# chinmay.net
KiCad netlist of a schematic drawn in EAGLE
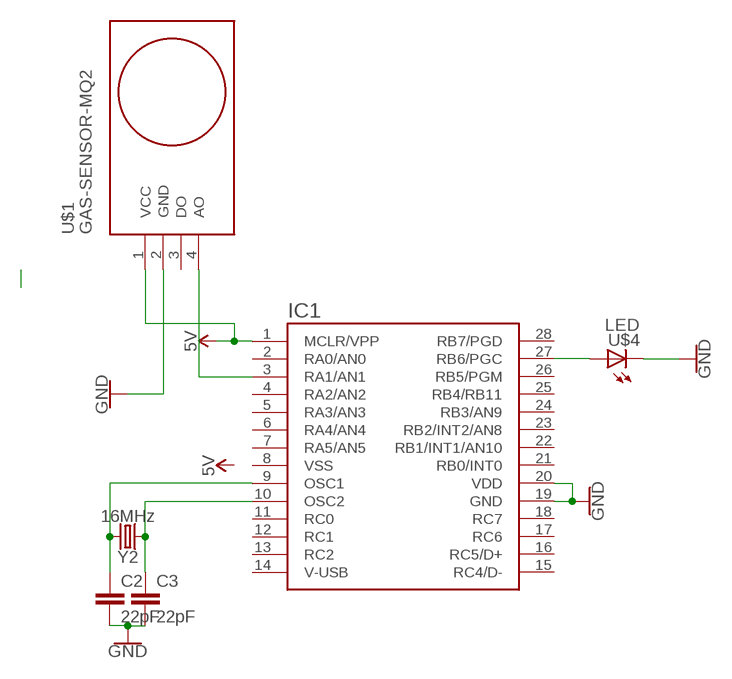
[diagram p0: schematic, sheet 1]

(export (version "E")
  (design (tool "Eeschema 10.0.6"))
  (components
    (comp (ref "C2")
      (value "22pF")
      (footprint "eagle-import:0603")
      (libsource (lib "eagle-import") (part "22PF-0603-50V-5%"))
    )
    (comp (ref "C3")
      (value "22pF")
      (footprint "eagle-import:0603")
      (libsource (lib "eagle-import") (part "22PF-0603-50V-5%"))
    )
    (comp (ref "IC1")
      (value "PIC18F2550SMD-28")
      (footprint "eagle-import:SO28")
      (libsource (lib "eagle-import") (part "PIC18F2550SMD-28"))
    )
    (comp (ref "U$1")
      (value "GAS-SENSOR-MQ2")
      (footprint "eagle-import:GAS-SENSOR-MQ2")
      (libsource (lib "eagle-import") (part "GAS-SENSOR-MQ2"))
    )
    (comp (ref "U$4")
      (value "LED")
      (footprint "eagle-import:HLMP-1790")
      (libsource (lib "eagle-import") (part "LED"))
    )
    (comp (ref "Y2")
      (value "16MHz")
      (footprint "eagle-import:HC49US")
      (libsource (lib "eagle-import") (part "CRYSTAL-16MHZPTH-HC49US"))
    )
  )
  (nets
    (net (code "1") (name "5V") (class "Default")
      (node (ref "IC1") (pin "1") (pinfunction "MCLR/VPP_1") (pintype "bidirectional"))
      (node (ref "U$1") (pin "1") (pinfunction "VCC_1") (pintype "power_in"))
    )
    (net (code "2") (name "GND") (class "Default")
      (node (ref "C2") (pin "2") (pinfunction "2_2") (pintype "passive"))
      (node (ref "C3") (pin "2") (pinfunction "2_2") (pintype "passive"))
      (node (ref "IC1") (pin "19") (pinfunction "GND_19") (pintype "bidirectional"))
      (node (ref "IC1") (pin "20") (pinfunction "VDD_20") (pintype "bidirectional"))
      (node (ref "U$1") (pin "2") (pinfunction "GND_2") (pintype "power_in"))
      (node (ref "U$4") (pin "C") (pinfunction "C_C") (pintype "passive"))
    )
    (net (code "3") (name "Net-(IC1-OSC1)") (class "Default")
      (node (ref "C2") (pin "1") (pinfunction "1_1") (pintype "passive"))
      (node (ref "IC1") (pin "9") (pinfunction "OSC1_9") (pintype "bidirectional"))
      (node (ref "Y2") (pin "2") (pinfunction "2_2") (pintype "passive"))
    )
    (net (code "4") (name "Net-(IC1-OSC2)") (class "Default")
      (node (ref "C3") (pin "1") (pinfunction "1_1") (pintype "passive"))
      (node (ref "IC1") (pin "10") (pinfunction "OSC2_10") (pintype "bidirectional"))
      (node (ref "Y2") (pin "1") (pinfunction "1_1") (pintype "passive"))
    )
    (net (code "5") (name "Net-(IC1-RA1{slash}AN1)") (class "Default")
      (node (ref "IC1") (pin "3") (pinfunction "RA1/AN1_3") (pintype "bidirectional"))
      (node (ref "U$1") (pin "4") (pinfunction "AO_4") (pintype "output"))
    )
    (net (code "6") (name "Net-(IC1-RB6{slash}PGC)") (class "Default")
      (node (ref "IC1") (pin "27") (pinfunction "RB6/PGC_27") (pintype "bidirectional"))
      (node (ref "U$4") (pin "A") (pinfunction "A_A") (pintype "passive"))
    )
    (net (code "7") (name "unconnected-(IC1-RA0{slash}AN0-Pad2)") (class "Default")
      (node (ref "IC1") (pin "2") (pinfunction "RA0/AN0_2") (pintype "bidirectional"))
    )
    (net (code "8") (name "unconnected-(IC1-RA2{slash}AN2-Pad4)") (class "Default")
      (node (ref "IC1") (pin "4") (pinfunction "RA2/AN2_4") (pintype "bidirectional"))
    )
    (net (code "9") (name "unconnected-(IC1-RA3{slash}AN3-Pad5)") (class "Default")
      (node (ref "IC1") (pin "5") (pinfunction "RA3/AN3_5") (pintype "bidirectional"))
    )
    (net (code "10") (name "unconnected-(IC1-RA4{slash}AN4-Pad6)") (class "Default")
      (node (ref "IC1") (pin "6") (pinfunction "RA4/AN4_6") (pintype "bidirectional"))
    )
    (net (code "11") (name "unconnected-(IC1-RA5{slash}AN5-Pad7)") (class "Default")
      (node (ref "IC1") (pin "7") (pinfunction "RA5/AN5_7") (pintype "bidirectional"))
    )
    (net (code "12") (name "unconnected-(IC1-RB0{slash}INT0-Pad21)") (class "Default")
      (node (ref "IC1") (pin "21") (pinfunction "RB0/INT0_21") (pintype "bidirectional"))
    )
    (net (code "13") (name "unconnected-(IC1-RB1{slash}INT1{slash}AN10-Pad22)") (class "Default")
      (node (ref "IC1") (pin "22") (pinfunction "RB1/INT1/AN10_22") (pintype "bidirectional"))
    )
    (net (code "14") (name "unconnected-(IC1-RB2{slash}INT2{slash}AN8-Pad23)") (class "Default")
      (node (ref "IC1") (pin "23") (pinfunction "RB2/INT2/AN8_23") (pintype "bidirectional"))
    )
    (net (code "15") (name "unconnected-(IC1-RB3{slash}AN9-Pad24)") (class "Default")
      (node (ref "IC1") (pin "24") (pinfunction "RB3/AN9_24") (pintype "bidirectional"))
    )
    (net (code "16") (name "unconnected-(IC1-RB4{slash}RB11-Pad25)") (class "Default")
      (node (ref "IC1") (pin "25") (pinfunction "RB4/RB11_25") (pintype "bidirectional"))
    )
    (net (code "17") (name "unconnected-(IC1-RB5{slash}PGM-Pad26)") (class "Default")
      (node (ref "IC1") (pin "26") (pinfunction "RB5/PGM_26") (pintype "bidirectional"))
    )
    (net (code "18") (name "unconnected-(IC1-RB7{slash}PGD-Pad28)") (class "Default")
      (node (ref "IC1") (pin "28") (pinfunction "RB7/PGD_28") (pintype "bidirectional"))
    )
    (net (code "19") (name "unconnected-(IC1-RC0-Pad11)") (class "Default")
      (node (ref "IC1") (pin "11") (pinfunction "RC0_11") (pintype "bidirectional"))
    )
    (net (code "20") (name "unconnected-(IC1-RC1-Pad12)") (class "Default")
      (node (ref "IC1") (pin "12") (pinfunction "RC1_12") (pintype "bidirectional"))
    )
    (net (code "21") (name "unconnected-(IC1-RC2-Pad13)") (class "Default")
      (node (ref "IC1") (pin "13") (pinfunction "RC2_13") (pintype "bidirectional"))
    )
    (net (code "22") (name "unconnected-(IC1-RC4{slash}D--Pad15)") (class "Default")
      (node (ref "IC1") (pin "15") (pinfunction "RC4/D-_15") (pintype "bidirectional"))
    )
    (net (code "23") (name "unconnected-(IC1-RC5{slash}D+-Pad16)") (class "Default")
      (node (ref "IC1") (pin "16") (pinfunction "RC5/D+_16") (pintype "bidirectional"))
    )
    (net (code "24") (name "unconnected-(IC1-RC6-Pad17)") (class "Default")
      (node (ref "IC1") (pin "17") (pinfunction "RC6_17") (pintype "bidirectional"))
    )
    (net (code "25") (name "unconnected-(IC1-RC7-Pad18)") (class "Default")
      (node (ref "IC1") (pin "18") (pinfunction "RC7_18") (pintype "bidirectional"))
    )
    (net (code "26") (name "unconnected-(IC1-V-USB-Pad14)") (class "Default")
      (node (ref "IC1") (pin "14") (pinfunction "V-USB_14") (pintype "bidirectional"))
    )
    (net (code "27") (name "unconnected-(IC1-VSS-Pad8)") (class "Default")
      (node (ref "IC1") (pin "8") (pinfunction "VSS_8") (pintype "bidirectional"))
    )
    (net (code "28") (name "unconnected-(U$1-DO-Pad3)") (class "Default")
      (node (ref "U$1") (pin "3") (pinfunction "DO_3") (pintype "output"))
    )
  )
)
